# spi_neopixel_rev2.net
KiCad netlist of a schematic drawn in EAGLE
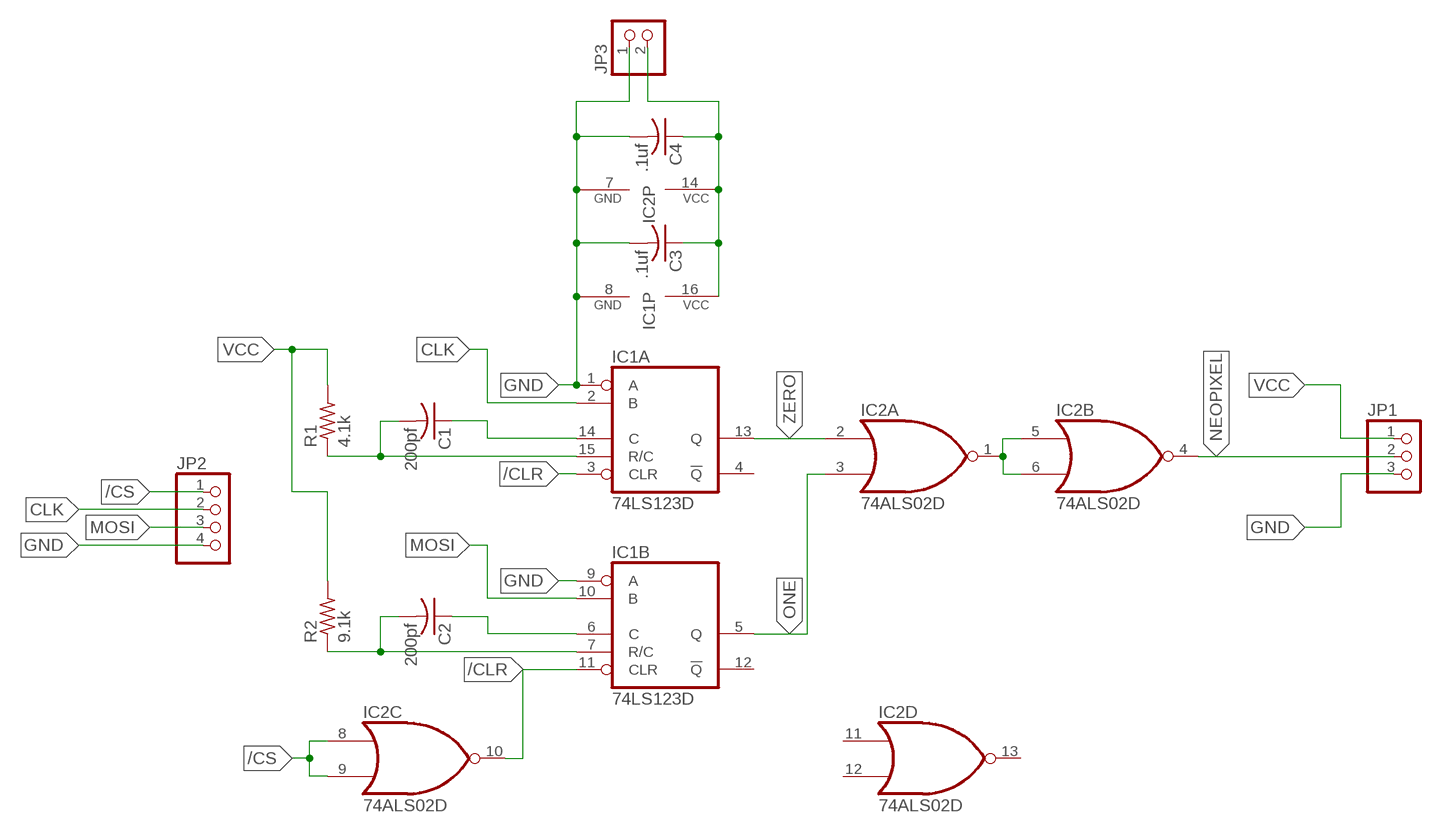
[diagram p0: schematic, sheet 1]

(export (version "E")
  (design (tool "Eeschema 10.0.6"))
  (components
    (comp (ref "C1")
      (value "200pf")
      (footprint "eagle-import:C0805")
      (libsource (lib "eagle-import") (part "C-USC0805"))
    )
    (comp (ref "C2")
      (value "200pf")
      (footprint "eagle-import:C0805")
      (libsource (lib "eagle-import") (part "C-USC0805"))
    )
    (comp (ref "C3")
      (value ".1uf")
      (footprint "eagle-import:C0805")
      (libsource (lib "eagle-import") (part "C-USC0805"))
    )
    (comp (ref "C4")
      (value ".1uf")
      (footprint "eagle-import:C0805")
      (libsource (lib "eagle-import") (part "C-USC0805"))
    )
    (comp (ref "IC1")
      (value "74LS123D")
      (footprint "eagle-import:SO16")
      (libsource (lib "eagle-import") (part "74123DLS"))
    )
    (comp (ref "IC2")
      (value "74ALS02D")
      (footprint "eagle-import:SO14")
      (libsource (lib "eagle-import") (part "7402DALS"))
    )
    (comp (ref "JP1")
      (value "PINHD-1X3")
      (footprint "eagle-import:1X03")
      (libsource (lib "eagle-import") (part "PINHD-1X3"))
    )
    (comp (ref "JP2")
      (value "PINHD-1X4")
      (footprint "eagle-import:1X04")
      (libsource (lib "eagle-import") (part "PINHD-1X4"))
    )
    (comp (ref "JP3")
      (value "PINHD-1X2")
      (footprint "eagle-import:1X02")
      (libsource (lib "eagle-import") (part "PINHD-1X2"))
    )
    (comp (ref "R1")
      (value "4.1k")
      (footprint "eagle-import:M0805")
      (libsource (lib "eagle-import") (part "R-US_M0805"))
    )
    (comp (ref "R2")
      (value "9.1k")
      (footprint "eagle-import:M0805")
      (libsource (lib "eagle-import") (part "R-US_M0805"))
    )
  )
  (nets
    (net (code "1") (name "CLK") (class "Default")
      (node (ref "IC1") (pin "2") (pinfunction "B_2") (pintype "input"))
      (node (ref "JP2") (pin "2") (pinfunction "2_2") (pintype "passive"))
    )
    (net (code "2") (name "GND") (class "Default")
      (node (ref "C3") (pin "2") (pinfunction "2_2") (pintype "passive"))
      (node (ref "C4") (pin "2") (pinfunction "2_2") (pintype "passive"))
      (node (ref "IC1") (pin "1") (pinfunction "A_1") (pintype "input"))
      (node (ref "IC1") (pin "8") (pinfunction "GND_8") (pintype "power_in"))
      (node (ref "IC1") (pin "9") (pinfunction "A_9") (pintype "input"))
      (node (ref "IC2") (pin "7") (pinfunction "GND_7") (pintype "power_in"))
      (node (ref "JP1") (pin "3") (pinfunction "3_3") (pintype "passive"))
      (node (ref "JP2") (pin "4") (pinfunction "4_4") (pintype "passive"))
      (node (ref "JP3") (pin "1") (pinfunction "1_1") (pintype "passive"))
    )
    (net (code "3") (name "MOSI") (class "Default")
      (node (ref "IC1") (pin "10") (pinfunction "B_10") (pintype "input"))
      (node (ref "JP2") (pin "3") (pinfunction "3_3") (pintype "passive"))
    )
    (net (code "4") (name "NEOPIXEL") (class "Default")
      (node (ref "IC2") (pin "4") (pinfunction "O_4") (pintype "output"))
      (node (ref "JP1") (pin "2") (pinfunction "2_2") (pintype "passive"))
    )
    (net (code "5") (name "Net-(IC1A-C)") (class "Default")
      (node (ref "C1") (pin "1") (pinfunction "1_1") (pintype "passive"))
      (node (ref "IC1") (pin "14") (pinfunction "C_14") (pintype "input"))
    )
    (net (code "6") (name "Net-(IC1A-R{slash}C)") (class "Default")
      (node (ref "C1") (pin "2") (pinfunction "2_2") (pintype "passive"))
      (node (ref "IC1") (pin "15") (pinfunction "R/C_15") (pintype "input"))
      (node (ref "R1") (pin "1") (pinfunction "1_1") (pintype "passive"))
    )
    (net (code "7") (name "Net-(IC1B-C)") (class "Default")
      (node (ref "C2") (pin "1") (pinfunction "1_1") (pintype "passive"))
      (node (ref "IC1") (pin "6") (pinfunction "C_6") (pintype "input"))
    )
    (net (code "8") (name "Net-(IC1B-R{slash}C)") (class "Default")
      (node (ref "C2") (pin "2") (pinfunction "2_2") (pintype "passive"))
      (node (ref "IC1") (pin "7") (pinfunction "R/C_7") (pintype "input"))
      (node (ref "R2") (pin "1") (pinfunction "1_1") (pintype "passive"))
    )
    (net (code "9") (name "Net-(IC2A-O)") (class "Default")
      (node (ref "IC2") (pin "1") (pinfunction "O_1") (pintype "output"))
      (node (ref "IC2") (pin "5") (pinfunction "I0_5") (pintype "input"))
      (node (ref "IC2") (pin "6") (pinfunction "I1_6") (pintype "input"))
    )
    (net (code "10") (name "ONE") (class "Default")
      (node (ref "IC1") (pin "5") (pinfunction "Q_5") (pintype "output"))
      (node (ref "IC2") (pin "3") (pinfunction "I1_3") (pintype "input"))
    )
    (net (code "11") (name "VCC") (class "Default")
      (node (ref "C3") (pin "1") (pinfunction "1_1") (pintype "passive"))
      (node (ref "C4") (pin "1") (pinfunction "1_1") (pintype "passive"))
      (node (ref "IC1") (pin "16") (pinfunction "VCC_16") (pintype "power_in"))
      (node (ref "IC2") (pin "14") (pinfunction "VCC_14") (pintype "power_in"))
      (node (ref "JP1") (pin "1") (pinfunction "1_1") (pintype "passive"))
      (node (ref "JP3") (pin "2") (pinfunction "2_2") (pintype "passive"))
      (node (ref "R1") (pin "2") (pinfunction "2_2") (pintype "passive"))
      (node (ref "R2") (pin "2") (pinfunction "2_2") (pintype "passive"))
    )
    (net (code "12") (name "ZERO") (class "Default")
      (node (ref "IC1") (pin "13") (pinfunction "Q_13") (pintype "output"))
      (node (ref "IC2") (pin "2") (pinfunction "I0_2") (pintype "input"))
    )
    (net (code "13") (name "unconnected-(IC1A-~{Q}-Pad4)") (class "Default")
      (node (ref "IC1") (pin "4") (pinfunction "~{Q}_4") (pintype "output"))
    )
    (net (code "14") (name "unconnected-(IC1B-~{Q}-Pad12)") (class "Default")
      (node (ref "IC1") (pin "12") (pinfunction "~{Q}_12") (pintype "output"))
    )
    (net (code "15") (name "unconnected-(IC2D-I0-Pad11)") (class "Default")
      (node (ref "IC2") (pin "11") (pinfunction "I0_11") (pintype "input"))
    )
    (net (code "16") (name "unconnected-(IC2D-I1-Pad12)") (class "Default")
      (node (ref "IC2") (pin "12") (pinfunction "I1_12") (pintype "input"))
    )
    (net (code "17") (name "unconnected-(IC2D-O-Pad13)") (class "Default")
      (node (ref "IC2") (pin "13") (pinfunction "O_13") (pintype "output"))
    )
    (net (code "18") (name "{slash}CLR") (class "Default")
      (node (ref "IC1") (pin "11") (pinfunction "CLR_11") (pintype "input"))
      (node (ref "IC1") (pin "3") (pinfunction "CLR_3") (pintype "input"))
      (node (ref "IC2") (pin "10") (pinfunction "O_10") (pintype "output"))
    )
    (net (code "19") (name "{slash}CS") (class "Default")
      (node (ref "IC2") (pin "8") (pinfunction "I0_8") (pintype "input"))
      (node (ref "IC2") (pin "9") (pinfunction "I1_9") (pintype "input"))
      (node (ref "JP2") (pin "1") (pinfunction "1_1") (pintype "passive"))
    )
  )
)
